# ASM2101.net
KiCad netlist of a schematic drawn in EAGLE
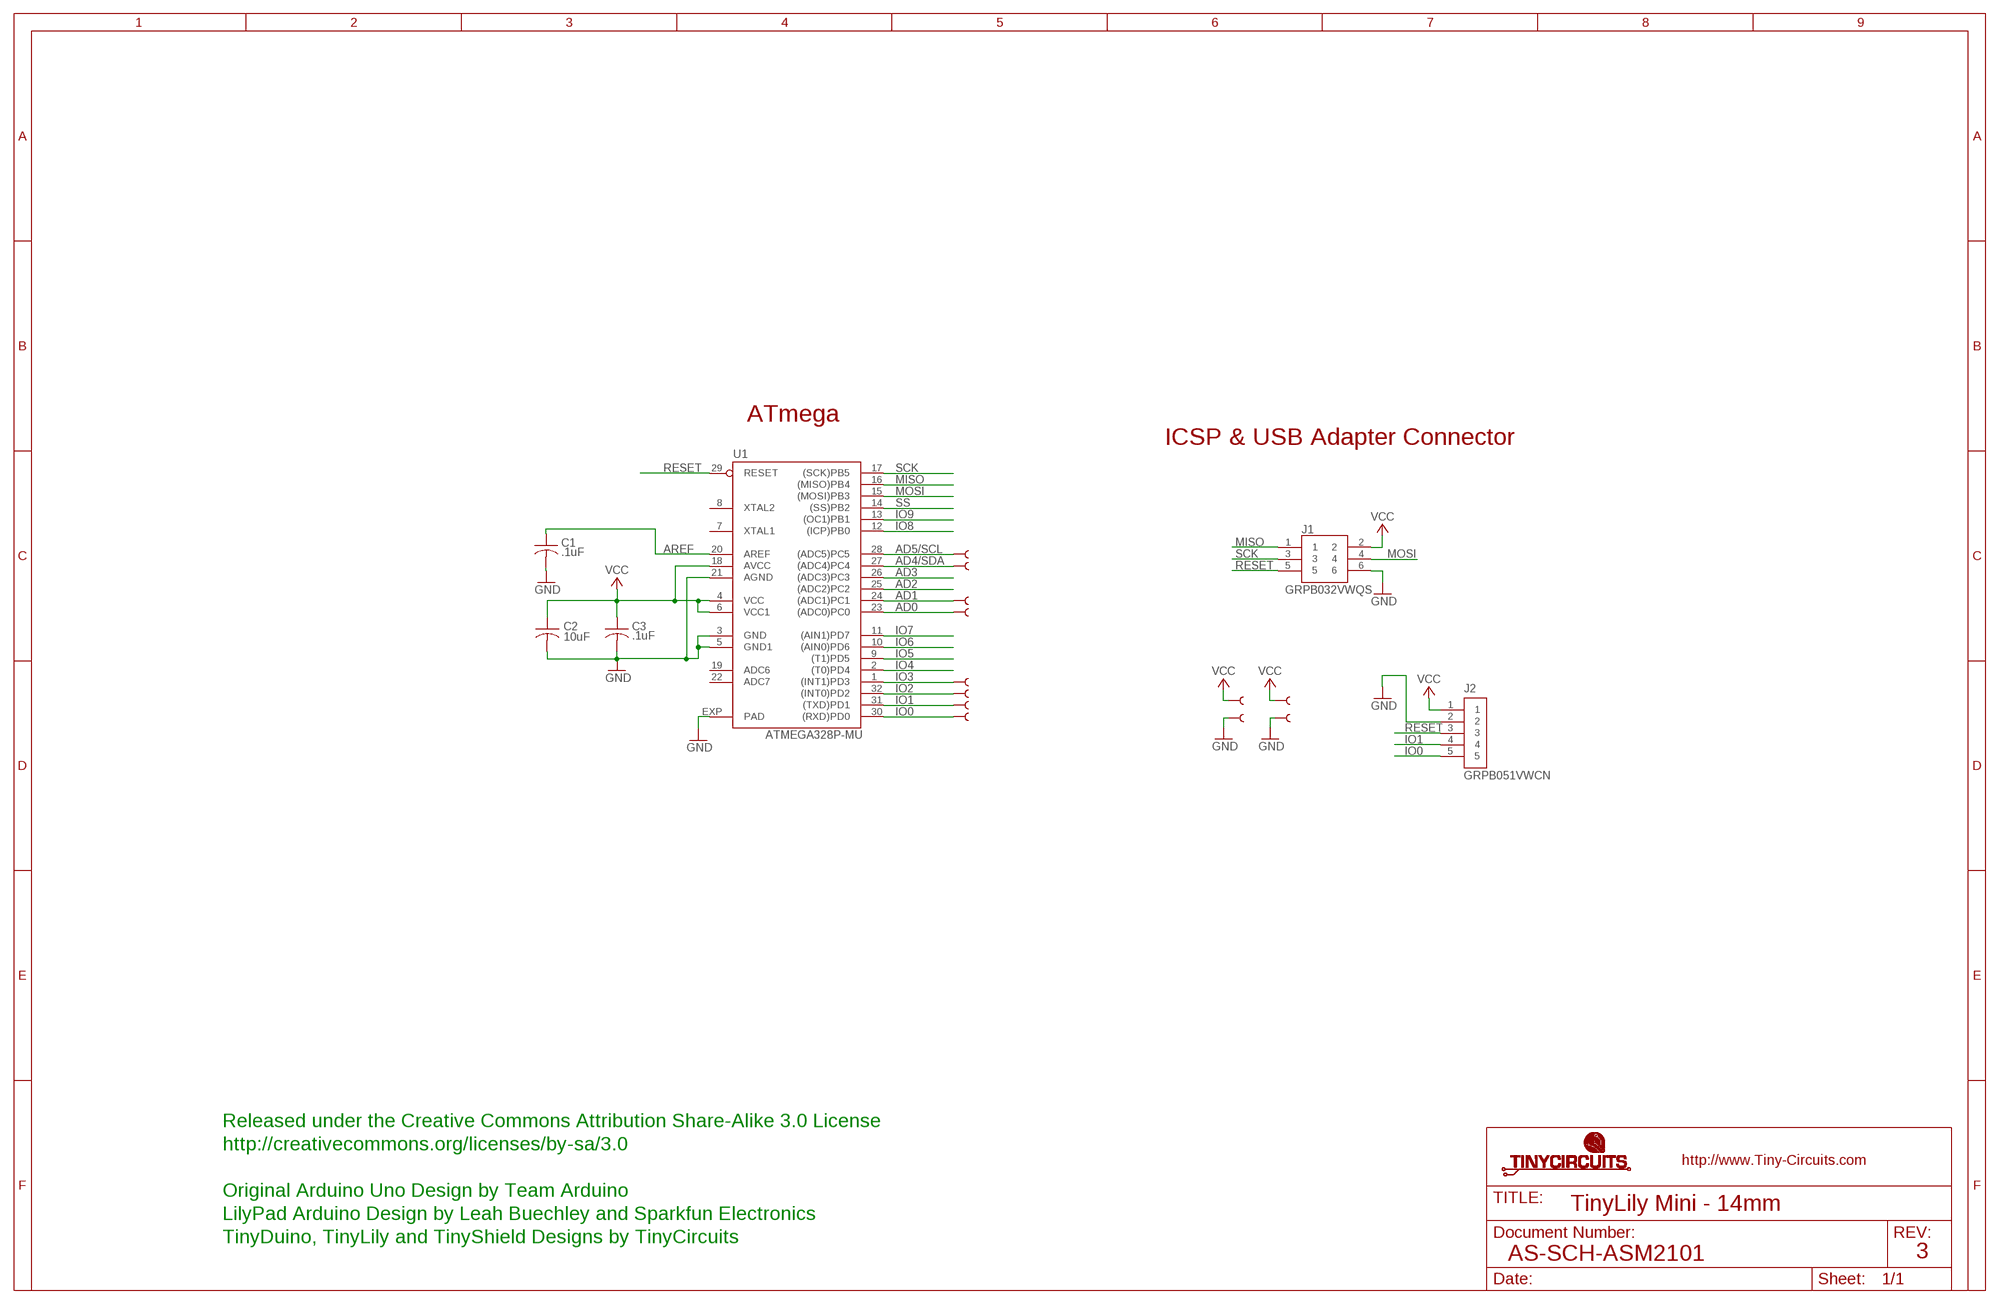
[diagram p0: schematic, sheet 1]

(export (version "E")
  (design (tool "Eeschema 10.0.6"))
  (components
    (comp (ref "$1")
      (value "SEWTAB")
      (footprint "eagle-import:SEWTAP_TH")
      (libsource (lib "eagle-import") (part "SEWTAB"))
    )
    (comp (ref "C1")
      (value ".1uF")
      (footprint "eagle-import:C0402")
      (fields (field (name "PARTNO") "AS-ITM-00008") (field (name "PARTNO_1") "AS-ITM-00008"))
      (libsource (lib "eagle-import") (part "AS-ITM-00008"))
    )
    (comp (ref "C2")
      (value "10uF")
      (footprint "eagle-import:C0603")
      (fields (field (name "PARTNO") "AS-ITM-00002") (field (name "PARTNO_1") "AS-ITM-00002"))
      (libsource (lib "eagle-import") (part "AS-ITM-00002"))
    )
    (comp (ref "C3")
      (value ".1uF")
      (footprint "eagle-import:C0402")
      (fields (field (name "PARTNO") "AS-ITM-00008") (field (name "PARTNO_1") "AS-ITM-00008"))
      (libsource (lib "eagle-import") (part "AS-ITM-00008"))
    )
    (comp (ref "J1")
      (value "GRPB032VWQS")
      (footprint "eagle-import:2X3_.05__SMT_HEADER")
      (fields (field (name "PARTNO") "AS-ITM-00034"))
      (libsource (lib "eagle-import") (part "AS-ITM-00034"))
    )
    (comp (ref "J2")
      (value "GRPB051VWCN")
      (footprint "eagle-import:1X5_.05_RA_TH_HEADER")
      (fields (field (name "PARTNO") "AS-ITM-00036"))
      (libsource (lib "eagle-import") (part "AS-ITM-00036"))
    )
    (comp (ref "U$1")
      (value "SEWTAB")
      (footprint "eagle-import:SEWTAP_TH")
      (libsource (lib "eagle-import") (part "SEWTAB"))
    )
    (comp (ref "U$2")
      (value "SEWTAB")
      (footprint "eagle-import:SEWTAP_TH")
      (libsource (lib "eagle-import") (part "SEWTAB"))
    )
    (comp (ref "U$3")
      (value "SEWTAB")
      (footprint "eagle-import:SEWTAP_TH")
      (libsource (lib "eagle-import") (part "SEWTAB"))
    )
    (comp (ref "U$4")
      (value "SEWTAB")
      (footprint "eagle-import:SEWTAP_TH")
      (libsource (lib "eagle-import") (part "SEWTAB"))
    )
    (comp (ref "U$5")
      (value "SEWTAB")
      (footprint "eagle-import:SEWTAP_TH")
      (libsource (lib "eagle-import") (part "SEWTAB"))
    )
    (comp (ref "U$7")
      (value "SEWTAB")
      (footprint "eagle-import:SEWTAP_TH")
      (libsource (lib "eagle-import") (part "SEWTAB"))
    )
    (comp (ref "U$8")
      (value "SEWTAB")
      (footprint "eagle-import:SEWTAP_TH")
      (libsource (lib "eagle-import") (part "SEWTAB"))
    )
    (comp (ref "U$9")
      (value "SEWTAB")
      (footprint "eagle-import:SEWTAP_TH")
      (libsource (lib "eagle-import") (part "SEWTAB"))
    )
    (comp (ref "U$10")
      (value "SEWTAB")
      (footprint "eagle-import:SEWTAP_TH")
      (libsource (lib "eagle-import") (part "SEWTAB"))
    )
    (comp (ref "U$11")
      (value "SEWTAB")
      (footprint "eagle-import:SEWTAP_TH")
      (libsource (lib "eagle-import") (part "SEWTAB"))
    )
    (comp (ref "U$12")
      (value "SEWTAB")
      (footprint "eagle-import:SEWTAP_TH")
      (libsource (lib "eagle-import") (part "SEWTAB"))
    )
    (comp (ref "U1")
      (value "ATMEGA328P-MU")
      (footprint "eagle-import:ATMEL_QFN32")
      (fields (field (name "PARTNO") "AS-ITM-00013") (field (name "PARTNO_1") "AS-ITM-00013"))
      (libsource (lib "eagle-import") (part "AS-ITM-00013MU"))
    )
  )
  (nets
    (net (code "1") (name "/AD0") (class "Default")
      (node (ref "U$4") (pin "1") (pinfunction "1_1") (pintype "bidirectional"))
      (node (ref "U1") (pin "23") (pinfunction "(ADC0)PC0_23") (pintype "bidirectional"))
    )
    (net (code "2") (name "/AD1") (class "Default")
      (node (ref "U$3") (pin "1") (pinfunction "1_1") (pintype "bidirectional"))
      (node (ref "U1") (pin "24") (pinfunction "(ADC1)PC1_24") (pintype "bidirectional"))
    )
    (net (code "3") (name "/AD2") (class "Default")
      (node (ref "U1") (pin "25") (pinfunction "(ADC2)PC2_25") (pintype "bidirectional"))
    )
    (net (code "4") (name "/AD3") (class "Default")
      (node (ref "U1") (pin "26") (pinfunction "(ADC3)PC3_26") (pintype "bidirectional"))
    )
    (net (code "5") (name "/AD4{slash}SDA") (class "Default")
      (node (ref "U$2") (pin "1") (pinfunction "1_1") (pintype "bidirectional"))
      (node (ref "U1") (pin "27") (pinfunction "(ADC4)PC4_27") (pintype "bidirectional"))
    )
    (net (code "6") (name "/AD5{slash}SCL") (class "Default")
      (node (ref "U$1") (pin "1") (pinfunction "1_1") (pintype "bidirectional"))
      (node (ref "U1") (pin "28") (pinfunction "(ADC5)PC5_28") (pintype "bidirectional"))
    )
    (net (code "7") (name "/AREF") (class "Default")
      (node (ref "C1") (pin "1") (pinfunction "1_1") (pintype "passive"))
      (node (ref "U1") (pin "20") (pinfunction "AREF_20") (pintype "passive"))
    )
    (net (code "8") (name "/IO0") (class "Default")
      (node (ref "J2") (pin "5") (pinfunction "5_5") (pintype "bidirectional"))
      (node (ref "U$10") (pin "1") (pinfunction "1_1") (pintype "bidirectional"))
      (node (ref "U1") (pin "30") (pinfunction "(RXD)PD0_30") (pintype "bidirectional"))
    )
    (net (code "9") (name "/IO1") (class "Default")
      (node (ref "J2") (pin "4") (pinfunction "4_4") (pintype "bidirectional"))
      (node (ref "U$9") (pin "1") (pinfunction "1_1") (pintype "bidirectional"))
      (node (ref "U1") (pin "31") (pinfunction "(TXD)PD1_31") (pintype "bidirectional"))
    )
    (net (code "10") (name "/IO2") (class "Default")
      (node (ref "$1") (pin "1") (pinfunction "1_1") (pintype "bidirectional"))
      (node (ref "U1") (pin "32") (pinfunction "(INT0)PD2_32") (pintype "bidirectional"))
    )
    (net (code "11") (name "/IO3") (class "Default")
      (node (ref "U$5") (pin "1") (pinfunction "1_1") (pintype "bidirectional"))
      (node (ref "U1") (pin "1") (pinfunction "(INT1)PD3_1") (pintype "bidirectional"))
    )
    (net (code "12") (name "/IO4") (class "Default")
      (node (ref "U1") (pin "2") (pinfunction "(T0)PD4_2") (pintype "bidirectional"))
    )
    (net (code "13") (name "/IO5") (class "Default")
      (node (ref "U1") (pin "9") (pinfunction "(T1)PD5_9") (pintype "bidirectional"))
    )
    (net (code "14") (name "/IO6") (class "Default")
      (node (ref "U1") (pin "10") (pinfunction "(AIN0)PD6_10") (pintype "bidirectional"))
    )
    (net (code "15") (name "/IO7") (class "Default")
      (node (ref "U1") (pin "11") (pinfunction "(AIN1)PD7_11") (pintype "bidirectional"))
    )
    (net (code "16") (name "/IO8") (class "Default")
      (node (ref "U1") (pin "12") (pinfunction "(ICP)PB0_12") (pintype "bidirectional"))
    )
    (net (code "17") (name "/IO9") (class "Default")
      (node (ref "U1") (pin "13") (pinfunction "(OC1)PB1_13") (pintype "bidirectional"))
    )
    (net (code "18") (name "/MISO") (class "Default")
      (node (ref "J1") (pin "1") (pinfunction "1_1") (pintype "bidirectional"))
      (node (ref "U1") (pin "16") (pinfunction "(MISO)PB4_16") (pintype "bidirectional"))
    )
    (net (code "19") (name "/MOSI") (class "Default")
      (node (ref "J1") (pin "4") (pinfunction "4_4") (pintype "bidirectional"))
      (node (ref "U1") (pin "15") (pinfunction "(MOSI)PB3_15") (pintype "bidirectional"))
    )
    (net (code "20") (name "/RESET") (class "Default")
      (node (ref "J1") (pin "5") (pinfunction "5_5") (pintype "bidirectional"))
      (node (ref "J2") (pin "3") (pinfunction "3_3") (pintype "bidirectional"))
      (node (ref "U1") (pin "29") (pinfunction "RESET_29") (pintype "input"))
    )
    (net (code "21") (name "/SCK") (class "Default")
      (node (ref "J1") (pin "3") (pinfunction "3_3") (pintype "bidirectional"))
      (node (ref "U1") (pin "17") (pinfunction "(SCK)PB5_17") (pintype "bidirectional"))
    )
    (net (code "22") (name "/SS") (class "Default")
      (node (ref "U1") (pin "14") (pinfunction "(SS)PB2_14") (pintype "bidirectional"))
    )
    (net (code "23") (name "GND") (class "Default")
      (node (ref "C1") (pin "2") (pinfunction "2_2") (pintype "passive"))
      (node (ref "C2") (pin "2") (pinfunction "2_2") (pintype "passive"))
      (node (ref "C3") (pin "2") (pinfunction "2_2") (pintype "passive"))
      (node (ref "J1") (pin "6") (pinfunction "6_6") (pintype "bidirectional"))
      (node (ref "J2") (pin "2") (pinfunction "2_2") (pintype "bidirectional"))
      (node (ref "U$11") (pin "1") (pinfunction "1_1") (pintype "bidirectional"))
      (node (ref "U$12") (pin "1") (pinfunction "1_1") (pintype "bidirectional"))
      (node (ref "U1") (pin "21") (pinfunction "AGND_21") (pintype "power_in"))
      (node (ref "U1") (pin "3") (pinfunction "GND_3") (pintype "power_in"))
      (node (ref "U1") (pin "5") (pinfunction "GND1_5") (pintype "power_in"))
      (node (ref "U1") (pin "EXP") (pinfunction "PAD_EXP") (pintype "power_in"))
    )
    (net (code "24") (name "VCC") (class "Default")
      (node (ref "C2") (pin "1") (pinfunction "1_1") (pintype "passive"))
      (node (ref "C3") (pin "1") (pinfunction "1_1") (pintype "passive"))
      (node (ref "J1") (pin "2") (pinfunction "2_2") (pintype "bidirectional"))
      (node (ref "J2") (pin "1") (pinfunction "1_1") (pintype "bidirectional"))
      (node (ref "U$7") (pin "1") (pinfunction "1_1") (pintype "bidirectional"))
      (node (ref "U$8") (pin "1") (pinfunction "1_1") (pintype "bidirectional"))
      (node (ref "U1") (pin "18") (pinfunction "AVCC_18") (pintype "power_in"))
      (node (ref "U1") (pin "4") (pinfunction "VCC_4") (pintype "power_in"))
      (node (ref "U1") (pin "6") (pinfunction "VCC1_6") (pintype "power_in"))
    )
    (net (code "25") (name "unconnected-(U1-ADC6-Pad19)") (class "Default")
      (node (ref "U1") (pin "19") (pinfunction "ADC6_19") (pintype "bidirectional"))
    )
    (net (code "26") (name "unconnected-(U1-ADC7-Pad22)") (class "Default")
      (node (ref "U1") (pin "22") (pinfunction "ADC7_22") (pintype "bidirectional"))
    )
    (net (code "27") (name "unconnected-(U1-XTAL1-Pad7)") (class "Default")
      (node (ref "U1") (pin "7") (pinfunction "XTAL1_7") (pintype "bidirectional"))
    )
    (net (code "28") (name "unconnected-(U1-XTAL2-Pad8)") (class "Default")
      (node (ref "U1") (pin "8") (pinfunction "XTAL2_8") (pintype "bidirectional"))
    )
  )
)
